# Coulomb_counter.net
KiCad netlist of a schematic drawn in EAGLE
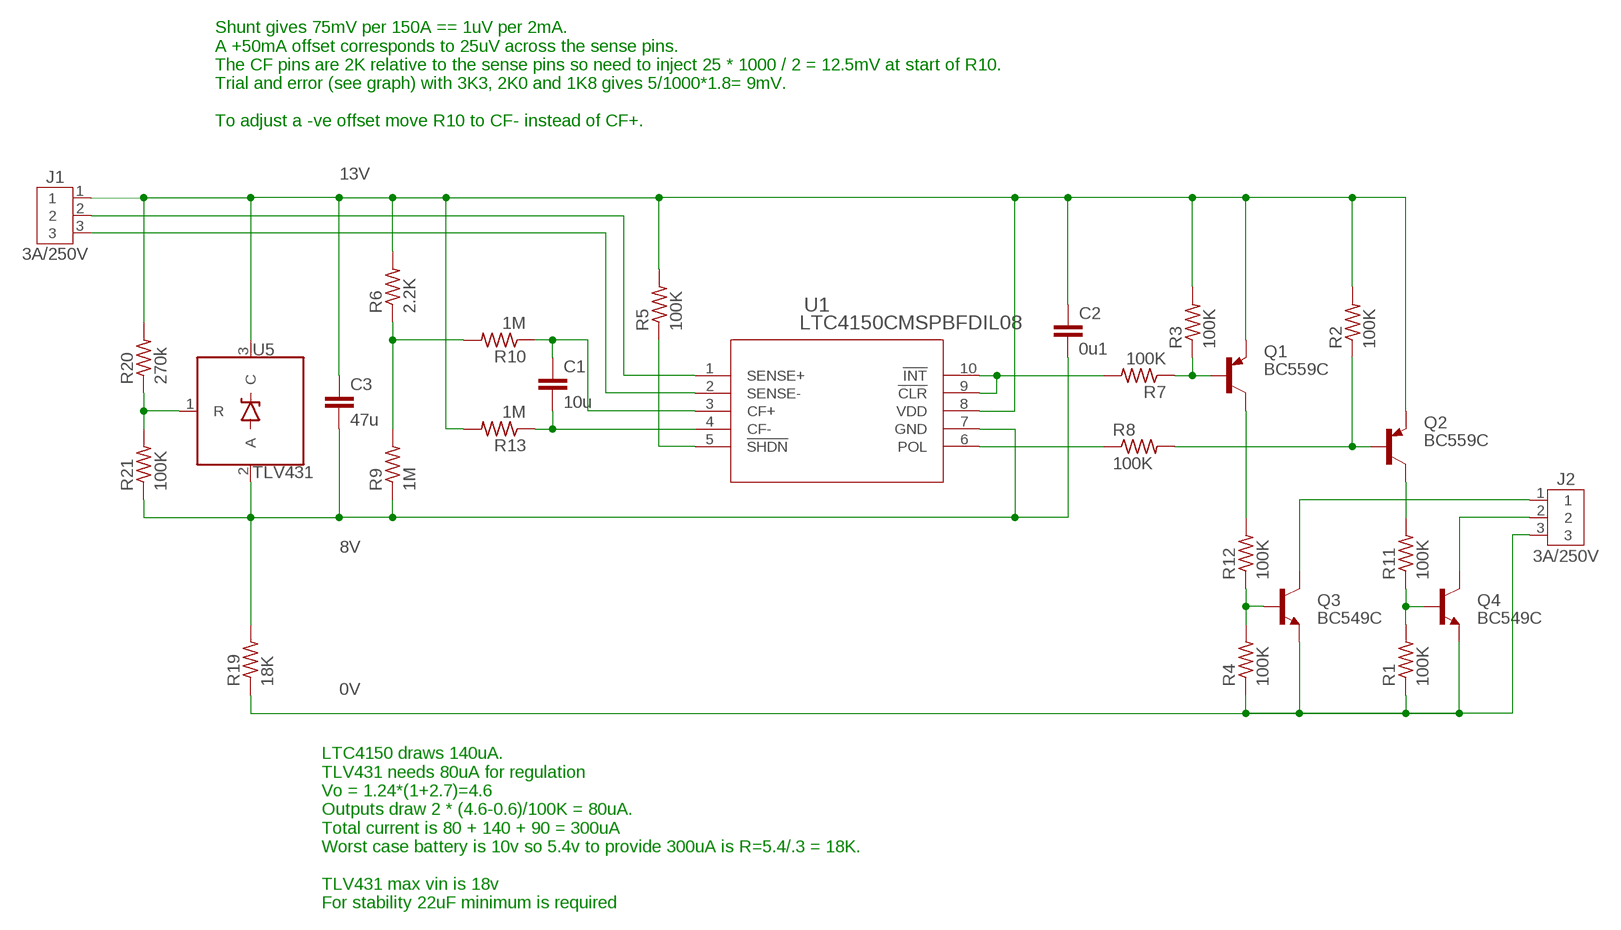
[diagram p0: schematic, sheet 1]

(export (version "E")
  (design (tool "Eeschema 10.0.6"))
  (components
    (comp (ref "C1")
      (value "10u")
      (footprint "eagle-import:C2.5-2")
      (libsource (lib "eagle-import") (part "C2.5/2"))
    )
    (comp (ref "C2")
      (value "0u1")
      (footprint "eagle-import:C2.5-2")
      (libsource (lib "eagle-import") (part "C2.5/2"))
    )
    (comp (ref "C3")
      (value "47u")
      (footprint "eagle-import:C2.5-2")
      (libsource (lib "eagle-import") (part "C2.5/2"))
    )
    (comp (ref "J1")
      (value "3A/250V")
      (footprint "eagle-import:B3B-XH-A")
      (fields (field (name "MANUFACTURER") "JST (XH connector)") (field (name "MPN") "B3B-XH-A"))
      (libsource (lib "eagle-import") (part "B3B-XH-A"))
    )
    (comp (ref "J2")
      (value "3A/250V")
      (footprint "eagle-import:B3B-XH-A")
      (fields (field (name "MANUFACTURER") "JST (XH connector)") (field (name "MPN") "B3B-XH-A"))
      (libsource (lib "eagle-import") (part "B3B-XH-A"))
    )
    (comp (ref "Q1")
      (value "BC559C")
      (footprint "eagle-import:TO92-EBC")
      (libsource (lib "eagle-import") (part "BC559C"))
    )
    (comp (ref "Q2")
      (value "BC559C")
      (footprint "eagle-import:TO92-EBC")
      (libsource (lib "eagle-import") (part "BC559C"))
    )
    (comp (ref "Q3")
      (value "BC549C")
      (footprint "eagle-import:TO92-EBC")
      (libsource (lib "eagle-import") (part "BC549C"))
    )
    (comp (ref "Q4")
      (value "BC549C")
      (footprint "eagle-import:TO92-EBC")
      (libsource (lib "eagle-import") (part "BC549C"))
    )
    (comp (ref "R1")
      (value "100K")
      (footprint "eagle-import:0204_7")
      (libsource (lib "eagle-import") (part "RES_7"))
    )
    (comp (ref "R2")
      (value "100K")
      (footprint "eagle-import:0204_7")
      (libsource (lib "eagle-import") (part "RES_7"))
    )
    (comp (ref "R3")
      (value "100K")
      (footprint "eagle-import:0204_7")
      (libsource (lib "eagle-import") (part "RES_7"))
    )
    (comp (ref "R4")
      (value "100K")
      (footprint "eagle-import:0204_7")
      (libsource (lib "eagle-import") (part "RES_7"))
    )
    (comp (ref "R5")
      (value "100K")
      (footprint "eagle-import:0204_7")
      (libsource (lib "eagle-import") (part "RES_7"))
    )
    (comp (ref "R6")
      (value "2.2K")
      (footprint "eagle-import:0204_7")
      (libsource (lib "eagle-import") (part "RES_7"))
    )
    (comp (ref "R7")
      (value "100K")
      (footprint "eagle-import:0204_7")
      (libsource (lib "eagle-import") (part "RES_7"))
    )
    (comp (ref "R8")
      (value "100K")
      (footprint "eagle-import:0204_7")
      (libsource (lib "eagle-import") (part "RES_7"))
    )
    (comp (ref "R9")
      (value "1M")
      (footprint "eagle-import:0204_7")
      (libsource (lib "eagle-import") (part "RES_7"))
    )
    (comp (ref "R10")
      (value "1M")
      (footprint "eagle-import:0204_7")
      (libsource (lib "eagle-import") (part "RES_7"))
    )
    (comp (ref "R11")
      (value "100K")
      (footprint "eagle-import:0204_7")
      (libsource (lib "eagle-import") (part "RES_7"))
    )
    (comp (ref "R12")
      (value "100K")
      (footprint "eagle-import:0204_7")
      (libsource (lib "eagle-import") (part "RES_7"))
    )
    (comp (ref "R13")
      (value "1M")
      (footprint "eagle-import:0204_7")
      (libsource (lib "eagle-import") (part "RES_7"))
    )
    (comp (ref "R19")
      (value "18K")
      (footprint "eagle-import:0204_7")
      (libsource (lib "eagle-import") (part "RES_7"))
    )
    (comp (ref "R20")
      (value "270k")
      (footprint "eagle-import:0204_7")
      (libsource (lib "eagle-import") (part "RES_7"))
    )
    (comp (ref "R21")
      (value "100K")
      (footprint "eagle-import:0204_7")
      (libsource (lib "eagle-import") (part "RES_7"))
    )
    (comp (ref "U1")
      (value "LTC4150CMSPBFDIL08")
      (footprint "eagle-import:DIL10")
      (libsource (lib "eagle-import") (part "LTC4150CMSPBFDIL08"))
    )
    (comp (ref "U5")
      (value "TLV431")
      (footprint "eagle-import:TO92")
      (libsource (lib "eagle-import") (part "TLV431"))
    )
  )
  (nets
    (net (code "1") (name "/0V") (class "Default")
      (node (ref "J2") (pin "3") (pinfunction "3_3") (pintype "bidirectional"))
      (node (ref "Q3") (pin "E") (pinfunction "E_E") (pintype "passive"))
      (node (ref "Q4") (pin "E") (pinfunction "E_E") (pintype "passive"))
      (node (ref "R1") (pin "1") (pinfunction "1_1") (pintype "passive"))
      (node (ref "R19") (pin "1") (pinfunction "1_1") (pintype "passive"))
      (node (ref "R4") (pin "1") (pinfunction "1_1") (pintype "passive"))
    )
    (net (code "2") (name "/8V") (class "Default")
      (node (ref "C2") (pin "2") (pinfunction "2_2") (pintype "passive"))
      (node (ref "C3") (pin "2") (pinfunction "2_2") (pintype "passive"))
      (node (ref "R19") (pin "2") (pinfunction "2_2") (pintype "passive"))
      (node (ref "R21") (pin "1") (pinfunction "1_1") (pintype "passive"))
      (node (ref "R9") (pin "1") (pinfunction "1_1") (pintype "passive"))
      (node (ref "U1") (pin "7") (pinfunction "GND_7") (pintype "power_in"))
      (node (ref "U5") (pin "2") (pinfunction "A_2") (pintype "bidirectional"))
    )
    (net (code "3") (name "/13V") (class "Default")
      (node (ref "C2") (pin "1") (pinfunction "1_1") (pintype "passive"))
      (node (ref "C3") (pin "1") (pinfunction "1_1") (pintype "passive"))
      (node (ref "J1") (pin "1") (pinfunction "1_1") (pintype "bidirectional"))
      (node (ref "Q1") (pin "E") (pinfunction "E_E") (pintype "passive"))
      (node (ref "Q2") (pin "E") (pinfunction "E_E") (pintype "passive"))
      (node (ref "R13") (pin "2") (pinfunction "2_2") (pintype "passive"))
      (node (ref "R2") (pin "2") (pinfunction "2_2") (pintype "passive"))
      (node (ref "R20") (pin "2") (pinfunction "2_2") (pintype "passive"))
      (node (ref "R3") (pin "2") (pinfunction "2_2") (pintype "passive"))
      (node (ref "R5") (pin "2") (pinfunction "2_2") (pintype "passive"))
      (node (ref "R6") (pin "2") (pinfunction "2_2") (pintype "passive"))
      (node (ref "U1") (pin "8") (pinfunction "VDD_8") (pintype "power_in"))
      (node (ref "U5") (pin "3") (pinfunction "C_3") (pintype "bidirectional"))
    )
    (net (code "4") (name "Net-(J2-Pad1)") (class "Default")
      (node (ref "J2") (pin "1") (pinfunction "1_1") (pintype "bidirectional"))
      (node (ref "Q3") (pin "C") (pinfunction "C_C") (pintype "passive"))
    )
    (net (code "5") (name "Net-(J2-Pad2)") (class "Default")
      (node (ref "J2") (pin "2") (pinfunction "2_2") (pintype "bidirectional"))
      (node (ref "Q4") (pin "C") (pinfunction "C_C") (pintype "passive"))
    )
    (net (code "6") (name "Net-(Q1-PadB)") (class "Default")
      (node (ref "Q1") (pin "B") (pinfunction "B_B") (pintype "passive"))
      (node (ref "R3") (pin "1") (pinfunction "1_1") (pintype "passive"))
      (node (ref "R7") (pin "1") (pinfunction "1_1") (pintype "passive"))
    )
    (net (code "7") (name "Net-(Q1-PadC)") (class "Default")
      (node (ref "Q1") (pin "C") (pinfunction "C_C") (pintype "passive"))
      (node (ref "R12") (pin "2") (pinfunction "2_2") (pintype "passive"))
    )
    (net (code "8") (name "Net-(Q2-PadB)") (class "Default")
      (node (ref "Q2") (pin "B") (pinfunction "B_B") (pintype "passive"))
      (node (ref "R2") (pin "1") (pinfunction "1_1") (pintype "passive"))
      (node (ref "R8") (pin "2") (pinfunction "2_2") (pintype "passive"))
    )
    (net (code "9") (name "Net-(Q2-PadC)") (class "Default")
      (node (ref "Q2") (pin "C") (pinfunction "C_C") (pintype "passive"))
      (node (ref "R11") (pin "2") (pinfunction "2_2") (pintype "passive"))
    )
    (net (code "10") (name "Net-(Q3-PadB)") (class "Default")
      (node (ref "Q3") (pin "B") (pinfunction "B_B") (pintype "passive"))
      (node (ref "R12") (pin "1") (pinfunction "1_1") (pintype "passive"))
      (node (ref "R4") (pin "2") (pinfunction "2_2") (pintype "passive"))
    )
    (net (code "11") (name "Net-(Q4-PadB)") (class "Default")
      (node (ref "Q4") (pin "B") (pinfunction "B_B") (pintype "passive"))
      (node (ref "R1") (pin "2") (pinfunction "2_2") (pintype "passive"))
      (node (ref "R11") (pin "1") (pinfunction "1_1") (pintype "passive"))
    )
    (net (code "12") (name "Net-(R10-Pad2)") (class "Default")
      (node (ref "R10") (pin "2") (pinfunction "2_2") (pintype "passive"))
      (node (ref "R6") (pin "1") (pinfunction "1_1") (pintype "passive"))
      (node (ref "R9") (pin "2") (pinfunction "2_2") (pintype "passive"))
    )
    (net (code "13") (name "Net-(U1-CF+)") (class "Default")
      (node (ref "C1") (pin "1") (pinfunction "1_1") (pintype "passive"))
      (node (ref "R10") (pin "1") (pinfunction "1_1") (pintype "passive"))
      (node (ref "U1") (pin "3") (pinfunction "CF+_3") (pintype "input"))
    )
    (net (code "14") (name "Net-(U1-CF-)") (class "Default")
      (node (ref "C1") (pin "2") (pinfunction "2_2") (pintype "passive"))
      (node (ref "R13") (pin "1") (pinfunction "1_1") (pintype "passive"))
      (node (ref "U1") (pin "4") (pinfunction "CF-_4") (pintype "input"))
    )
    (net (code "15") (name "Net-(U1-POL)") (class "Default")
      (node (ref "R8") (pin "1") (pinfunction "1_1") (pintype "passive"))
      (node (ref "U1") (pin "6") (pinfunction "POL_6") (pintype "output"))
    )
    (net (code "16") (name "Net-(U1-SENSE+)") (class "Default")
      (node (ref "J1") (pin "2") (pinfunction "2_2") (pintype "bidirectional"))
      (node (ref "U1") (pin "1") (pinfunction "SENSE+_1") (pintype "input"))
    )
    (net (code "17") (name "Net-(U1-SENSE-)") (class "Default")
      (node (ref "J1") (pin "3") (pinfunction "3_3") (pintype "bidirectional"))
      (node (ref "U1") (pin "2") (pinfunction "SENSE-_2") (pintype "input"))
    )
    (net (code "18") (name "Net-(U1-~{CLR})") (class "Default")
      (node (ref "R7") (pin "2") (pinfunction "2_2") (pintype "passive"))
      (node (ref "U1") (pin "10") (pinfunction "~{INT}_10") (pintype "output"))
      (node (ref "U1") (pin "9") (pinfunction "~{CLR}_9") (pintype "input"))
    )
    (net (code "19") (name "Net-(U1-~{SHDN})") (class "Default")
      (node (ref "R5") (pin "1") (pinfunction "1_1") (pintype "passive"))
      (node (ref "U1") (pin "5") (pinfunction "~{SHDN}_5") (pintype "input"))
    )
    (net (code "20") (name "Net-(U5-R)") (class "Default")
      (node (ref "R20") (pin "1") (pinfunction "1_1") (pintype "passive"))
      (node (ref "R21") (pin "2") (pinfunction "2_2") (pintype "passive"))
      (node (ref "U5") (pin "1") (pinfunction "R_1") (pintype "bidirectional"))
    )
  )
)
